# PROC051C_Tempsensor.net
KiCad netlist of a schematic drawn in Altium Designer
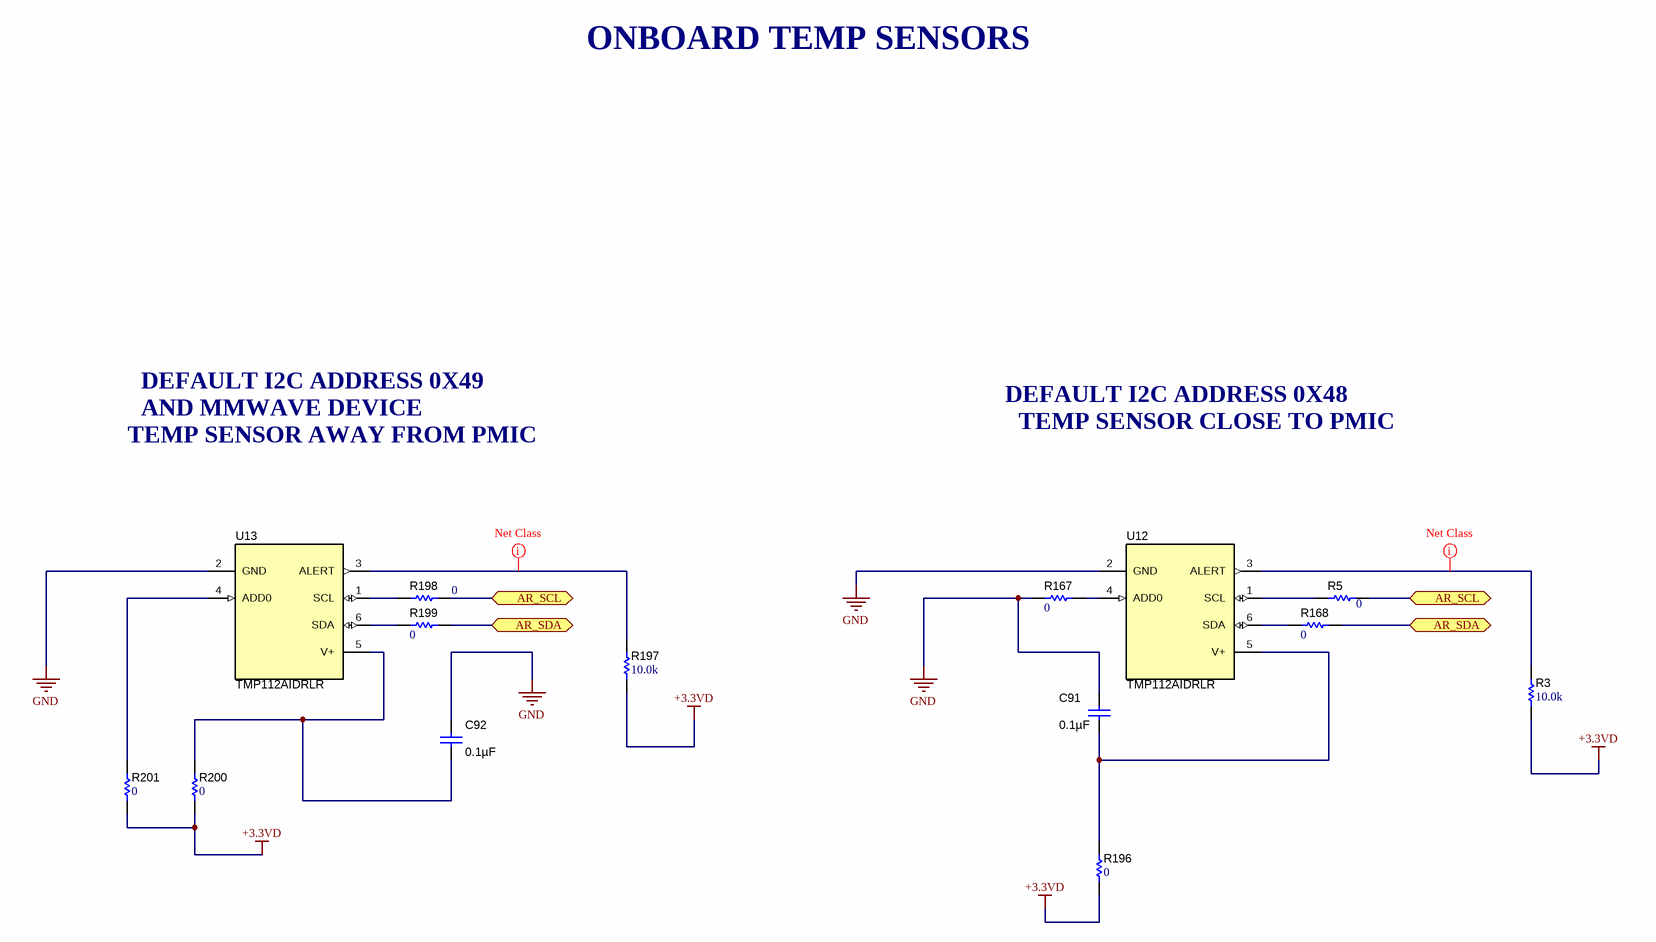
[diagram p0: PROC051C_Tempsensor.SchDoc]

(export (version "E")
  (design (tool "Eeschema 10.0.6"))
  (components
    (comp (ref "C91")
      (value "C0402C104K8RACTU")
      (footprint "0402L")
      (description "CAP, CERM, 0.1 µF, 10 V,+/- 10%, X7R, 0402")
      (fields (field (name "MANUFACTURER") "Kemet") (field (name "VALUEDISPLAYED") "0.1µF"))
      (libsource (lib "Altium Vault - TI") (part "Capacitor"))
    )
    (comp (ref "C92")
      (value "C0402C104K8RACTU")
      (footprint "0402L")
      (description "CAP, CERM, 0.1 µF, 10 V,+/- 10%, X7R, 0402")
      (fields (field (name "MANUFACTURER") "Kemet") (field (name "VALUEDISPLAYED") "0.1µF"))
      (libsource (lib "Altium Vault - TI") (part "Capacitor"))
    )
    (comp (ref "R3")
      (value "CRCW040210K0FKED")
      (footprint "0402L")
      (description "RES, 10.0 k, 1%, 0.063 W, AEC-Q200 Grade 0, 0402")
      (fields (field (name "MANUFACTURER") "Vishay-Dale") (field (name "VALUEDISPLAYED") "10.0k"))
      (libsource (lib "Altium Vault - TI") (part "Resistor"))
    )
    (comp (ref "R5")
      (value "CRCW02010000Z0ED")
      (footprint "0201_Silk")
      (description "RES, 0, 5%, 0.05 W, 0201")
      (fields (field (name "MANUFACTURER") "Vishay-Dale") (field (name "VALUEDISPLAYED") "0"))
      (libsource (lib "Altium Vault - TI") (part "Resistor"))
    )
    (comp (ref "R167")
      (value "CRCW02010000Z0ED")
      (footprint "0201_Silk")
      (description "RES, 0, 5%, 0.05 W, 0201")
      (fields (field (name "MANUFACTURER") "Vishay-Dale") (field (name "VALUEDISPLAYED") "0"))
      (libsource (lib "Altium Vault - TI") (part "Resistor"))
    )
    (comp (ref "R168")
      (value "CRCW02010000Z0ED")
      (footprint "0201_Silk")
      (description "RES, 0, 5%, 0.05 W, 0201")
      (fields (field (name "MANUFACTURER") "Vishay-Dale") (field (name "VALUEDISPLAYED") "0"))
      (libsource (lib "Altium Vault - TI") (part "Resistor"))
    )
    (comp (ref "R196")
      (value "ERJ-2GE0R00X")
      (footprint "0402L")
      (description "RES, 0, 5%, 0.1 W, AEC-Q200 Grade 0, 0402")
      (fields (field (name "MANUFACTURER") "Panasonic") (field (name "VALUEDISPLAYED") "0"))
      (libsource (lib "Altium Vault - TI") (part "Resistor"))
    )
    (comp (ref "R197")
      (value "CRCW040210K0FKED")
      (footprint "0402L")
      (description "RES, 10.0 k, 1%, 0.063 W, AEC-Q200 Grade 0, 0402")
      (fields (field (name "MANUFACTURER") "Vishay-Dale") (field (name "VALUEDISPLAYED") "10.0k"))
      (libsource (lib "Altium Vault - TI") (part "Resistor"))
    )
    (comp (ref "R198")
      (value "CRCW02010000Z0ED")
      (footprint "0201_Silk")
      (description "RES, 0, 5%, 0.05 W, 0201")
      (fields (field (name "MANUFACTURER") "Vishay-Dale") (field (name "VALUEDISPLAYED") "0"))
      (libsource (lib "Altium Vault - TI") (part "Resistor"))
    )
    (comp (ref "R199")
      (value "CRCW02010000Z0ED")
      (footprint "0201_Silk")
      (description "RES, 0, 5%, 0.05 W, 0201")
      (fields (field (name "MANUFACTURER") "Vishay-Dale") (field (name "VALUEDISPLAYED") "0"))
      (libsource (lib "Altium Vault - TI") (part "Resistor"))
    )
    (comp (ref "R200")
      (value "ERJ-2GE0R00X")
      (footprint "0402L")
      (description "RES, 0, 5%, 0.1 W, AEC-Q200 Grade 0, 0402")
      (fields (field (name "MANUFACTURER") "Panasonic") (field (name "VALUEDISPLAYED") "0"))
      (libsource (lib "Altium Vault - TI") (part "Resistor"))
    )
    (comp (ref "R201")
      (value "CRCW02010000Z0ED")
      (footprint "0201_Silk")
      (description "RES, 0, 5%, 0.05 W, 0201")
      (fields (field (name "MANUFACTURER") "Vishay-Dale") (field (name "VALUEDISPLAYED") "0"))
      (libsource (lib "Altium Vault - TI") (part "Resistor"))
    )
    (comp (ref "U12")
      (value "TMP112AIDRLR")
      (footprint "DRL0006A")
      (fields
        (field (name "ALTERNATE PARTNUMBER") "TMP112AIDRLT")
        (field (name "MANUFACTURER") "Texas Instruments")
        (field (name "PARTNUMBER") "TMP112AIDRLR")
        (field (name "PUBLISHER") "Texas Instruments")
      )
      (libsource (lib "Altium Vault - TI") (part "TMP112"))
    )
    (comp (ref "U13")
      (value "TMP112AIDRLR")
      (footprint "DRL0006A")
      (fields
        (field (name "ALTERNATE PARTNUMBER") "TMP112AIDRLT")
        (field (name "MANUFACTURER") "Texas Instruments")
        (field (name "PARTNUMBER") "TMP112AIDRLR")
        (field (name "PUBLISHER") "Texas Instruments")
      )
      (libsource (lib "Altium Vault - TI") (part "TMP112"))
    )
  )
  (nets
    (net (code "1") (name "+3.3VD") (class "Default")
      (node (ref "R196") (pin "2") (pinfunction "2_2") (pintype "passive"))
      (node (ref "R197") (pin "2") (pinfunction "2_2") (pintype "passive"))
      (node (ref "R200") (pin "2") (pinfunction "2_2") (pintype "passive"))
      (node (ref "R201") (pin "2") (pinfunction "2_2") (pintype "passive"))
      (node (ref "R3") (pin "2") (pinfunction "2_2") (pintype "passive"))
    )
    (net (code "2") (name "/AR_SCL") (class "Default")
      (node (ref "R198") (pin "1") (pinfunction "1_1") (pintype "passive"))
      (node (ref "R5") (pin "1") (pinfunction "1_1") (pintype "passive"))
    )
    (net (code "3") (name "/AR_SDA") (class "Default")
      (node (ref "R168") (pin "2") (pinfunction "2_2") (pintype "passive"))
      (node (ref "R199") (pin "2") (pinfunction "2_2") (pintype "passive"))
    )
    (net (code "4") (name "GND") (class "Default")
      (node (ref "C91") (pin "1") (pinfunction "1_1") (pintype "passive"))
      (node (ref "C92") (pin "1") (pinfunction "1_1") (pintype "passive"))
      (node (ref "R167") (pin "1") (pinfunction "1_1") (pintype "passive"))
      (node (ref "U12") (pin "2") (pinfunction "GND_2") (pintype "power_in"))
      (node (ref "U13") (pin "2") (pinfunction "GND_2") (pintype "power_in"))
    )
    (net (code "5") (name "Net-(U12-ADD0)") (class "Default")
      (node (ref "R167") (pin "2") (pinfunction "2_2") (pintype "passive"))
      (node (ref "U12") (pin "4") (pinfunction "ADD0_4") (pintype "input"))
    )
    (net (code "6") (name "Net-(U12-ALERT)") (class "Default")
      (node (ref "R3") (pin "1") (pinfunction "1_1") (pintype "passive"))
      (node (ref "U12") (pin "3") (pinfunction "ALERT_3") (pintype "output"))
    )
    (net (code "7") (name "Net-(U12-SCL)") (class "Default")
      (node (ref "R5") (pin "2") (pinfunction "2_2") (pintype "passive"))
      (node (ref "U12") (pin "1") (pinfunction "SCL_1") (pintype "bidirectional"))
    )
    (net (code "8") (name "Net-(U12-SDA)") (class "Default")
      (node (ref "R168") (pin "1") (pinfunction "1_1") (pintype "passive"))
      (node (ref "U12") (pin "6") (pinfunction "SDA_6") (pintype "bidirectional"))
    )
    (net (code "9") (name "Net-(U12-V+)") (class "Default")
      (node (ref "C91") (pin "2") (pinfunction "2_2") (pintype "passive"))
      (node (ref "R196") (pin "1") (pinfunction "1_1") (pintype "passive"))
      (node (ref "U12") (pin "5") (pinfunction "V+_5") (pintype "power_in"))
    )
    (net (code "10") (name "Net-(U13-ADD0)") (class "Default")
      (node (ref "R201") (pin "1") (pinfunction "1_1") (pintype "passive"))
      (node (ref "U13") (pin "4") (pinfunction "ADD0_4") (pintype "input"))
    )
    (net (code "11") (name "Net-(U13-ALERT)") (class "Default")
      (node (ref "R197") (pin "1") (pinfunction "1_1") (pintype "passive"))
      (node (ref "U13") (pin "3") (pinfunction "ALERT_3") (pintype "output"))
    )
    (net (code "12") (name "Net-(U13-SCL)") (class "Default")
      (node (ref "R198") (pin "2") (pinfunction "2_2") (pintype "passive"))
      (node (ref "U13") (pin "1") (pinfunction "SCL_1") (pintype "bidirectional"))
    )
    (net (code "13") (name "Net-(U13-SDA)") (class "Default")
      (node (ref "R199") (pin "1") (pinfunction "1_1") (pintype "passive"))
      (node (ref "U13") (pin "6") (pinfunction "SDA_6") (pintype "bidirectional"))
    )
    (net (code "14") (name "Net-(U13-V+)") (class "Default")
      (node (ref "C92") (pin "2") (pinfunction "2_2") (pintype "passive"))
      (node (ref "R200") (pin "1") (pinfunction "1_1") (pintype "passive"))
      (node (ref "U13") (pin "5") (pinfunction "V+_5") (pintype "power_in"))
    )
  )
)
